# TMS320F28379D_I2C.net
KiCad netlist of a schematic drawn in Altium Designer
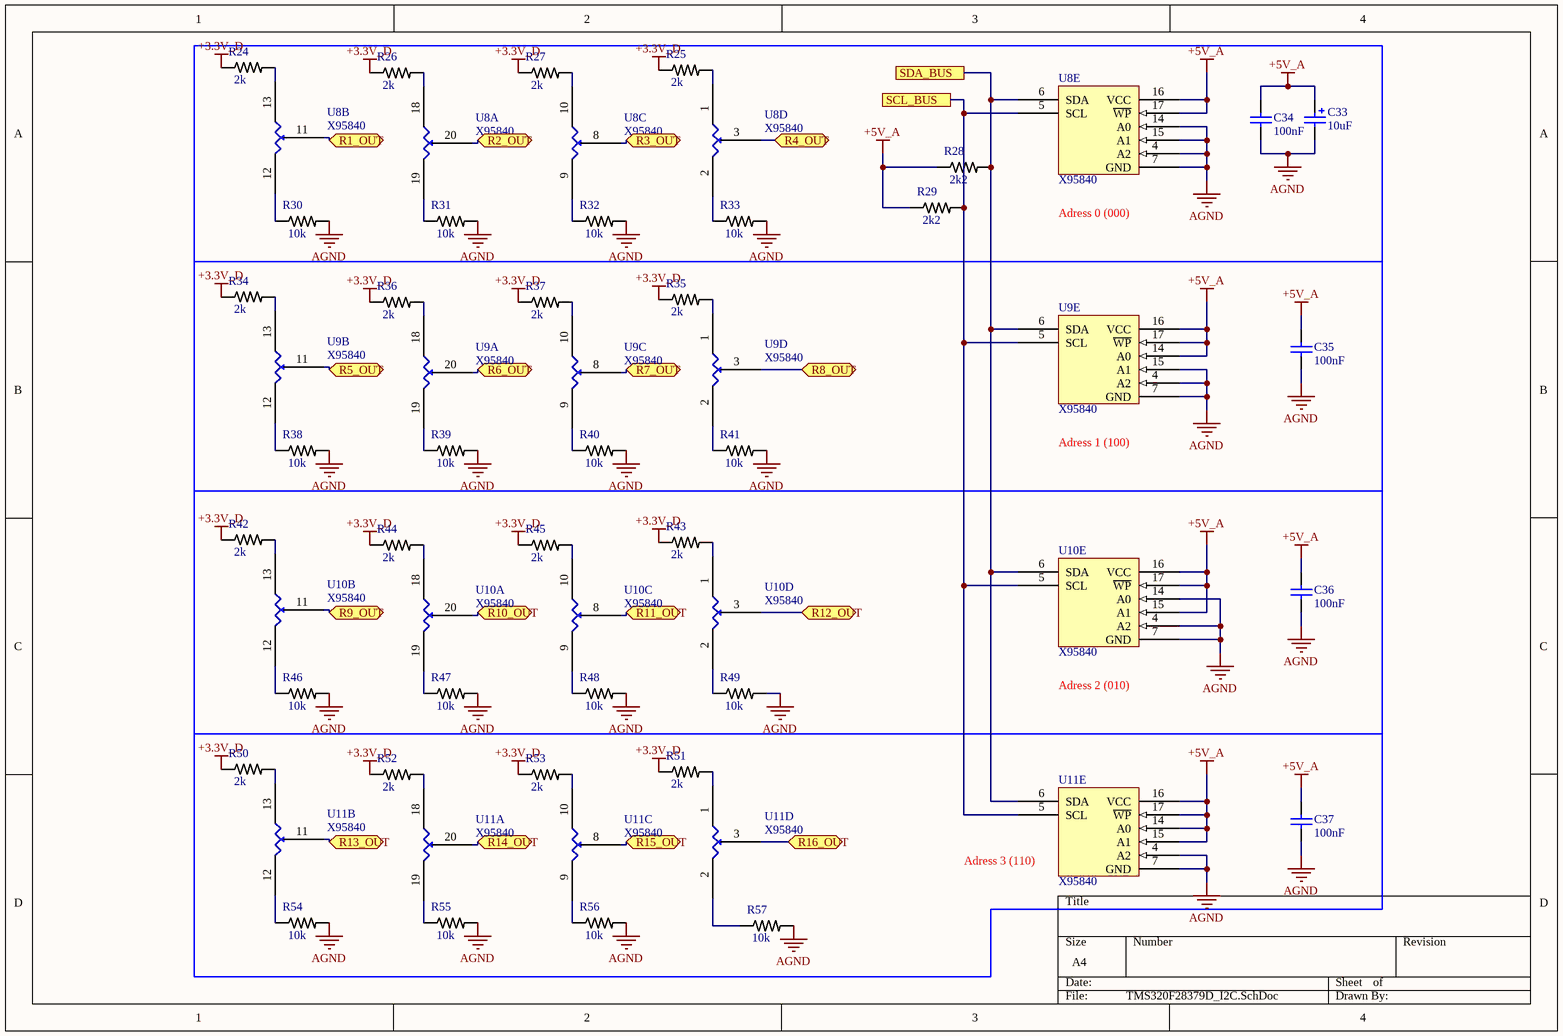
[diagram p0: TMS320F28379D_I2C.SchDoc]

(export (version "E")
  (design (tool "Eeschema 10.0.6"))
  (components
    (comp (ref "C33")
      (value "10uF")
      (footprint "Cap tantalio B")
      (fields (field (name "Comment") "Cap polarizado"))
      (libsource (lib "Condensadores") (part "Cap polarizado"))
    )
    (comp (ref "C34")
      (value "100nF")
      (footprint "CAP 0805")
      (fields (field (name "Comment") "Cap cerámico"))
      (libsource (lib "Condensadores") (part "Cap cerámico"))
    )
    (comp (ref "C35")
      (value "100nF")
      (footprint "CAP 0805")
      (fields (field (name "Comment") "Cap cerámico"))
      (libsource (lib "Condensadores") (part "Cap cerámico"))
    )
    (comp (ref "C36")
      (value "100nF")
      (footprint "CAP 0805")
      (fields (field (name "Comment") "Cap cerámico"))
      (libsource (lib "Condensadores") (part "Cap cerámico"))
    )
    (comp (ref "C37")
      (value "100nF")
      (footprint "CAP 0805")
      (fields (field (name "Comment") "Cap cerámico"))
      (libsource (lib "Condensadores") (part "Cap cerámico"))
    )
    (comp (ref "R24")
      (value "2k")
      (footprint "Resistor 0805")
      (description "Resistor")
      (fields (field (name "Comment") "Resistor 0805"))
      (libsource (lib "Resistencias") (part "Resistor"))
    )
    (comp (ref "R25")
      (value "2k")
      (footprint "Resistor 0805")
      (description "Resistor")
      (fields (field (name "Comment") "Resistor 0805"))
      (libsource (lib "Resistencias") (part "Resistor"))
    )
    (comp (ref "R26")
      (value "2k")
      (footprint "Resistor 0805")
      (description "Resistor")
      (fields (field (name "Comment") "Resistor 0805"))
      (libsource (lib "Resistencias") (part "Resistor"))
    )
    (comp (ref "R27")
      (value "2k")
      (footprint "Resistor 0805")
      (description "Resistor")
      (fields (field (name "Comment") "Resistor 0805"))
      (libsource (lib "Resistencias") (part "Resistor"))
    )
    (comp (ref "R28")
      (value "2k2")
      (footprint "Resistor 0805")
      (description "Resistor")
      (fields (field (name "Comment") "Resistor 0805"))
      (libsource (lib "Resistencias") (part "Resistor"))
    )
    (comp (ref "R29")
      (value "2k2")
      (footprint "Resistor 0805")
      (description "Resistor")
      (fields (field (name "Comment") "Resistor 0805"))
      (libsource (lib "Resistencias") (part "Resistor"))
    )
    (comp (ref "R30")
      (value "10k")
      (footprint "Resistor 0805")
      (description "Resistor")
      (fields (field (name "Comment") "Resistor 0805"))
      (libsource (lib "Resistencias") (part "Resistor"))
    )
    (comp (ref "R31")
      (value "10k")
      (footprint "Resistor 0805")
      (description "Resistor")
      (fields (field (name "Comment") "Resistor 0805"))
      (libsource (lib "Resistencias") (part "Resistor"))
    )
    (comp (ref "R32")
      (value "10k")
      (footprint "Resistor 0805")
      (description "Resistor")
      (fields (field (name "Comment") "Resistor 0805"))
      (libsource (lib "Resistencias") (part "Resistor"))
    )
    (comp (ref "R33")
      (value "10k")
      (footprint "Resistor 0805")
      (description "Resistor")
      (fields (field (name "Comment") "Resistor 0805"))
      (libsource (lib "Resistencias") (part "Resistor"))
    )
    (comp (ref "R34")
      (value "2k")
      (footprint "Resistor 0805")
      (description "Resistor")
      (fields (field (name "Comment") "Resistor 0805"))
      (libsource (lib "Resistencias") (part "Resistor"))
    )
    (comp (ref "R35")
      (value "2k")
      (footprint "Resistor 0805")
      (description "Resistor")
      (fields (field (name "Comment") "Resistor 0805"))
      (libsource (lib "Resistencias") (part "Resistor"))
    )
    (comp (ref "R36")
      (value "2k")
      (footprint "Resistor 0805")
      (description "Resistor")
      (fields (field (name "Comment") "Resistor 0805"))
      (libsource (lib "Resistencias") (part "Resistor"))
    )
    (comp (ref "R37")
      (value "2k")
      (footprint "Resistor 0805")
      (description "Resistor")
      (fields (field (name "Comment") "Resistor 0805"))
      (libsource (lib "Resistencias") (part "Resistor"))
    )
    (comp (ref "R38")
      (value "10k")
      (footprint "Resistor 0805")
      (description "Resistor")
      (fields (field (name "Comment") "Resistor 0805"))
      (libsource (lib "Resistencias") (part "Resistor"))
    )
    (comp (ref "R39")
      (value "10k")
      (footprint "Resistor 0805")
      (description "Resistor")
      (fields (field (name "Comment") "Resistor 0805"))
      (libsource (lib "Resistencias") (part "Resistor"))
    )
    (comp (ref "R40")
      (value "10k")
      (footprint "Resistor 0805")
      (description "Resistor")
      (fields (field (name "Comment") "Resistor 0805"))
      (libsource (lib "Resistencias") (part "Resistor"))
    )
    (comp (ref "R41")
      (value "10k")
      (footprint "Resistor 0805")
      (description "Resistor")
      (fields (field (name "Comment") "Resistor 0805"))
      (libsource (lib "Resistencias") (part "Resistor"))
    )
    (comp (ref "R42")
      (value "2k")
      (footprint "Resistor 0805")
      (description "Resistor")
      (fields (field (name "Comment") "Resistor 0805"))
      (libsource (lib "Resistencias") (part "Resistor"))
    )
    (comp (ref "R43")
      (value "2k")
      (footprint "Resistor 0805")
      (description "Resistor")
      (fields (field (name "Comment") "Resistor 0805"))
      (libsource (lib "Resistencias") (part "Resistor"))
    )
    (comp (ref "R44")
      (value "2k")
      (footprint "Resistor 0805")
      (description "Resistor")
      (fields (field (name "Comment") "Resistor 0805"))
      (libsource (lib "Resistencias") (part "Resistor"))
    )
    (comp (ref "R45")
      (value "2k")
      (footprint "Resistor 0805")
      (description "Resistor")
      (fields (field (name "Comment") "Resistor 0805"))
      (libsource (lib "Resistencias") (part "Resistor"))
    )
    (comp (ref "R46")
      (value "10k")
      (footprint "Resistor 0805")
      (description "Resistor")
      (fields (field (name "Comment") "Resistor 0805"))
      (libsource (lib "Resistencias") (part "Resistor"))
    )
    (comp (ref "R47")
      (value "10k")
      (footprint "Resistor 0805")
      (description "Resistor")
      (fields (field (name "Comment") "Resistor 0805"))
      (libsource (lib "Resistencias") (part "Resistor"))
    )
    (comp (ref "R48")
      (value "10k")
      (footprint "Resistor 0805")
      (description "Resistor")
      (fields (field (name "Comment") "Resistor 0805"))
      (libsource (lib "Resistencias") (part "Resistor"))
    )
    (comp (ref "R49")
      (value "10k")
      (footprint "Resistor 0805")
      (description "Resistor")
      (fields (field (name "Comment") "Resistor 0805"))
      (libsource (lib "Resistencias") (part "Resistor"))
    )
    (comp (ref "R50")
      (value "2k")
      (footprint "Resistor 0805")
      (description "Resistor")
      (fields (field (name "Comment") "Resistor 0805"))
      (libsource (lib "Resistencias") (part "Resistor"))
    )
    (comp (ref "R51")
      (value "2k")
      (footprint "Resistor 0805")
      (description "Resistor")
      (fields (field (name "Comment") "Resistor 0805"))
      (libsource (lib "Resistencias") (part "Resistor"))
    )
    (comp (ref "R52")
      (value "2k")
      (footprint "Resistor 0805")
      (description "Resistor")
      (fields (field (name "Comment") "Resistor 0805"))
      (libsource (lib "Resistencias") (part "Resistor"))
    )
    (comp (ref "R53")
      (value "2k")
      (footprint "Resistor 0805")
      (description "Resistor")
      (fields (field (name "Comment") "Resistor 0805"))
      (libsource (lib "Resistencias") (part "Resistor"))
    )
    (comp (ref "R54")
      (value "10k")
      (footprint "Resistor 0805")
      (description "Resistor")
      (fields (field (name "Comment") "Resistor 0805"))
      (libsource (lib "Resistencias") (part "Resistor"))
    )
    (comp (ref "R55")
      (value "10k")
      (footprint "Resistor 0805")
      (description "Resistor")
      (fields (field (name "Comment") "Resistor 0805"))
      (libsource (lib "Resistencias") (part "Resistor"))
    )
    (comp (ref "R56")
      (value "10k")
      (footprint "Resistor 0805")
      (description "Resistor")
      (fields (field (name "Comment") "Resistor 0805"))
      (libsource (lib "Resistencias") (part "Resistor"))
    )
    (comp (ref "R57")
      (value "10k")
      (footprint "Resistor 0805")
      (description "Resistor")
      (fields (field (name "Comment") "Resistor 0805"))
      (libsource (lib "Resistencias") (part "Resistor"))
    )
    (comp (ref "U8")
      (value "X95840")
      (footprint "20-TSSOP")
      (fields
        (field (name "DIGI-KEY PART NUMBER") "X95840WV20IZ-2.7-ND")
        (field (name "MANUFACTURER PART NUMBER") "X95840WV20IZ-2.7")
      )
      (libsource (lib "Circuitos integrados") (part "X95840"))
    )
    (comp (ref "U9")
      (value "X95840")
      (footprint "20-TSSOP")
      (fields
        (field (name "DIGI-KEY PART NUMBER") "X95840WV20IZ-2.7-ND")
        (field (name "MANUFACTURER PART NUMBER") "X95840WV20IZ-2.7")
      )
      (libsource (lib "Circuitos integrados") (part "X95840"))
    )
    (comp (ref "U10")
      (value "X95840")
      (footprint "20-TSSOP")
      (fields
        (field (name "DIGI-KEY PART NUMBER") "X95840WV20IZ-2.7-ND")
        (field (name "MANUFACTURER PART NUMBER") "X95840WV20IZ-2.7")
      )
      (libsource (lib "Circuitos integrados") (part "X95840"))
    )
    (comp (ref "U11")
      (value "X95840")
      (footprint "20-TSSOP")
      (fields
        (field (name "DIGI-KEY PART NUMBER") "X95840WV20IZ-2.7-ND")
        (field (name "MANUFACTURER PART NUMBER") "X95840WV20IZ-2.7")
      )
      (libsource (lib "Circuitos integrados") (part "X95840"))
    )
  )
  (nets
    (net (code "1") (name "+3.3V_D") (class "Default")
      (node (ref "R24") (pin "1") (pinfunction "1_1") (pintype "passive"))
      (node (ref "R25") (pin "1") (pinfunction "1_1") (pintype "passive"))
      (node (ref "R26") (pin "1") (pinfunction "1_1") (pintype "passive"))
      (node (ref "R27") (pin "1") (pinfunction "1_1") (pintype "passive"))
      (node (ref "R34") (pin "1") (pinfunction "1_1") (pintype "passive"))
      (node (ref "R35") (pin "1") (pinfunction "1_1") (pintype "passive"))
      (node (ref "R36") (pin "1") (pinfunction "1_1") (pintype "passive"))
      (node (ref "R37") (pin "1") (pinfunction "1_1") (pintype "passive"))
      (node (ref "R42") (pin "1") (pinfunction "1_1") (pintype "passive"))
      (node (ref "R43") (pin "1") (pinfunction "1_1") (pintype "passive"))
      (node (ref "R44") (pin "1") (pinfunction "1_1") (pintype "passive"))
      (node (ref "R45") (pin "1") (pinfunction "1_1") (pintype "passive"))
      (node (ref "R50") (pin "1") (pinfunction "1_1") (pintype "passive"))
      (node (ref "R51") (pin "1") (pinfunction "1_1") (pintype "passive"))
      (node (ref "R52") (pin "1") (pinfunction "1_1") (pintype "passive"))
      (node (ref "R53") (pin "1") (pinfunction "1_1") (pintype "passive"))
    )
    (net (code "2") (name "+5V_A") (class "Default")
      (node (ref "C33") (pin "1") (pinfunction "1_1") (pintype "passive"))
      (node (ref "C34") (pin "1") (pinfunction "1_1") (pintype "passive"))
      (node (ref "C35") (pin "1") (pinfunction "1_1") (pintype "passive"))
      (node (ref "C36") (pin "1") (pinfunction "1_1") (pintype "passive"))
      (node (ref "C37") (pin "1") (pinfunction "1_1") (pintype "passive"))
      (node (ref "R28") (pin "1") (pinfunction "1_1") (pintype "passive"))
      (node (ref "R29") (pin "1") (pinfunction "1_1") (pintype "passive"))
      (node (ref "U10") (pin "15") (pinfunction "A1_15") (pintype "input"))
      (node (ref "U10") (pin "16") (pinfunction "VCC_16") (pintype "power_in"))
      (node (ref "U10") (pin "17") (pinfunction "~{WP}_17") (pintype "input"))
      (node (ref "U11") (pin "14") (pinfunction "A0_14") (pintype "input"))
      (node (ref "U11") (pin "15") (pinfunction "A1_15") (pintype "input"))
      (node (ref "U11") (pin "16") (pinfunction "VCC_16") (pintype "power_in"))
      (node (ref "U11") (pin "17") (pinfunction "~{WP}_17") (pintype "input"))
      (node (ref "U8") (pin "16") (pinfunction "VCC_16") (pintype "power_in"))
      (node (ref "U8") (pin "17") (pinfunction "~{WP}_17") (pintype "input"))
      (node (ref "U9") (pin "14") (pinfunction "A0_14") (pintype "input"))
      (node (ref "U9") (pin "16") (pinfunction "VCC_16") (pintype "power_in"))
      (node (ref "U9") (pin "17") (pinfunction "~{WP}_17") (pintype "input"))
    )
    (net (code "3") (name "/R1_OUT") (class "Default")
      (node (ref "U8") (pin "11") (pinfunction "RW1_11") (pintype "passive"))
    )
    (net (code "4") (name "/R2_OUT") (class "Default")
      (node (ref "U8") (pin "20") (pinfunction "20_20") (pintype "passive"))
    )
    (net (code "5") (name "/R3_OUT") (class "Default")
      (node (ref "U8") (pin "8") (pinfunction "RW2_8") (pintype "passive"))
    )
    (net (code "6") (name "/R4_OUT") (class "Default")
      (node (ref "U8") (pin "3") (pinfunction "RW3_3") (pintype "passive"))
    )
    (net (code "7") (name "/R5_OUT") (class "Default")
      (node (ref "U9") (pin "11") (pinfunction "RW1_11") (pintype "passive"))
    )
    (net (code "8") (name "/R6_OUT") (class "Default")
      (node (ref "U9") (pin "20") (pinfunction "20_20") (pintype "passive"))
    )
    (net (code "9") (name "/R7_OUT") (class "Default")
      (node (ref "U9") (pin "8") (pinfunction "RW2_8") (pintype "passive"))
    )
    (net (code "10") (name "/R8_OUT") (class "Default")
      (node (ref "U9") (pin "3") (pinfunction "RW3_3") (pintype "passive"))
    )
    (net (code "11") (name "/R9_OUT") (class "Default")
      (node (ref "U10") (pin "11") (pinfunction "RW1_11") (pintype "passive"))
    )
    (net (code "12") (name "/R10_OUT") (class "Default")
      (node (ref "U10") (pin "20") (pinfunction "20_20") (pintype "passive"))
    )
    (net (code "13") (name "/R11_OUT") (class "Default")
      (node (ref "U10") (pin "8") (pinfunction "RW2_8") (pintype "passive"))
    )
    (net (code "14") (name "/R12_OUT") (class "Default")
      (node (ref "U10") (pin "3") (pinfunction "RW3_3") (pintype "passive"))
    )
    (net (code "15") (name "/R13_OUT") (class "Default")
      (node (ref "U11") (pin "11") (pinfunction "RW1_11") (pintype "passive"))
    )
    (net (code "16") (name "/R14_OUT") (class "Default")
      (node (ref "U11") (pin "20") (pinfunction "20_20") (pintype "passive"))
    )
    (net (code "17") (name "/R15_OUT") (class "Default")
      (node (ref "U11") (pin "8") (pinfunction "RW2_8") (pintype "passive"))
    )
    (net (code "18") (name "/R16_OUT") (class "Default")
      (node (ref "U11") (pin "3") (pinfunction "RW3_3") (pintype "passive"))
    )
    (net (code "19") (name "/SCL_BUS") (class "Default")
      (node (ref "R29") (pin "2") (pinfunction "2_2") (pintype "passive"))
      (node (ref "U10") (pin "5") (pinfunction "SCL_5") (pintype "passive"))
      (node (ref "U11") (pin "5") (pinfunction "SCL_5") (pintype "passive"))
      (node (ref "U8") (pin "5") (pinfunction "SCL_5") (pintype "passive"))
      (node (ref "U9") (pin "5") (pinfunction "SCL_5") (pintype "passive"))
    )
    (net (code "20") (name "/SDA_BUS") (class "Default")
      (node (ref "R28") (pin "2") (pinfunction "2_2") (pintype "passive"))
      (node (ref "U10") (pin "6") (pinfunction "SDA_6") (pintype "passive"))
      (node (ref "U11") (pin "6") (pinfunction "SDA_6") (pintype "passive"))
      (node (ref "U8") (pin "6") (pinfunction "SDA_6") (pintype "passive"))
      (node (ref "U9") (pin "6") (pinfunction "SDA_6") (pintype "passive"))
    )
    (net (code "21") (name "AGND") (class "Default")
      (node (ref "C33") (pin "2") (pinfunction "2_2") (pintype "passive"))
      (node (ref "C34") (pin "2") (pinfunction "2_2") (pintype "passive"))
      (node (ref "C35") (pin "2") (pinfunction "2_2") (pintype "passive"))
      (node (ref "C36") (pin "2") (pinfunction "2_2") (pintype "passive"))
      (node (ref "C37") (pin "2") (pinfunction "2_2") (pintype "passive"))
      (node (ref "R30") (pin "2") (pinfunction "2_2") (pintype "passive"))
      (node (ref "R31") (pin "2") (pinfunction "2_2") (pintype "passive"))
      (node (ref "R32") (pin "2") (pinfunction "2_2") (pintype "passive"))
      (node (ref "R33") (pin "2") (pinfunction "2_2") (pintype "passive"))
      (node (ref "R38") (pin "2") (pinfunction "2_2") (pintype "passive"))
      (node (ref "R39") (pin "2") (pinfunction "2_2") (pintype "passive"))
      (node (ref "R40") (pin "2") (pinfunction "2_2") (pintype "passive"))
      (node (ref "R41") (pin "2") (pinfunction "2_2") (pintype "passive"))
      (node (ref "R46") (pin "2") (pinfunction "2_2") (pintype "passive"))
      (node (ref "R47") (pin "2") (pinfunction "2_2") (pintype "passive"))
      (node (ref "R48") (pin "2") (pinfunction "2_2") (pintype "passive"))
      (node (ref "R49") (pin "2") (pinfunction "2_2") (pintype "passive"))
      (node (ref "R54") (pin "2") (pinfunction "2_2") (pintype "passive"))
      (node (ref "R55") (pin "2") (pinfunction "2_2") (pintype "passive"))
      (node (ref "R56") (pin "2") (pinfunction "2_2") (pintype "passive"))
      (node (ref "R57") (pin "2") (pinfunction "2_2") (pintype "passive"))
      (node (ref "U10") (pin "14") (pinfunction "A0_14") (pintype "input"))
      (node (ref "U10") (pin "4") (pinfunction "A2_4") (pintype "input"))
      (node (ref "U10") (pin "7") (pinfunction "GND_7") (pintype "power_in"))
      (node (ref "U11") (pin "4") (pinfunction "A2_4") (pintype "input"))
      (node (ref "U11") (pin "7") (pinfunction "GND_7") (pintype "power_in"))
      (node (ref "U8") (pin "14") (pinfunction "A0_14") (pintype "input"))
      (node (ref "U8") (pin "15") (pinfunction "A1_15") (pintype "input"))
      (node (ref "U8") (pin "4") (pinfunction "A2_4") (pintype "input"))
      (node (ref "U8") (pin "7") (pinfunction "GND_7") (pintype "power_in"))
      (node (ref "U9") (pin "15") (pinfunction "A1_15") (pintype "input"))
      (node (ref "U9") (pin "4") (pinfunction "A2_4") (pintype "input"))
      (node (ref "U9") (pin "7") (pinfunction "GND_7") (pintype "power_in"))
    )
    (net (code "22") (name "Net-(R26-Pad2)") (class "Default")
      (node (ref "R26") (pin "2") (pinfunction "2_2") (pintype "passive"))
      (node (ref "U8") (pin "18") (pinfunction "18_18") (pintype "passive"))
    )
    (net (code "23") (name "Net-(R31-Pad1)") (class "Default")
      (node (ref "R31") (pin "1") (pinfunction "1_1") (pintype "passive"))
      (node (ref "U8") (pin "19") (pinfunction "19_19") (pintype "passive"))
    )
    (net (code "24") (name "Net-(R36-Pad2)") (class "Default")
      (node (ref "R36") (pin "2") (pinfunction "2_2") (pintype "passive"))
      (node (ref "U9") (pin "18") (pinfunction "18_18") (pintype "passive"))
    )
    (net (code "25") (name "Net-(R39-Pad1)") (class "Default")
      (node (ref "R39") (pin "1") (pinfunction "1_1") (pintype "passive"))
      (node (ref "U9") (pin "19") (pinfunction "19_19") (pintype "passive"))
    )
    (net (code "26") (name "Net-(R44-Pad2)") (class "Default")
      (node (ref "R44") (pin "2") (pinfunction "2_2") (pintype "passive"))
      (node (ref "U10") (pin "18") (pinfunction "18_18") (pintype "passive"))
    )
    (net (code "27") (name "Net-(R47-Pad1)") (class "Default")
      (node (ref "R47") (pin "1") (pinfunction "1_1") (pintype "passive"))
      (node (ref "U10") (pin "19") (pinfunction "19_19") (pintype "passive"))
    )
    (net (code "28") (name "Net-(R52-Pad2)") (class "Default")
      (node (ref "R52") (pin "2") (pinfunction "2_2") (pintype "passive"))
      (node (ref "U11") (pin "18") (pinfunction "18_18") (pintype "passive"))
    )
    (net (code "29") (name "Net-(R55-Pad1)") (class "Default")
      (node (ref "R55") (pin "1") (pinfunction "1_1") (pintype "passive"))
      (node (ref "U11") (pin "19") (pinfunction "19_19") (pintype "passive"))
    )
    (net (code "30") (name "Net-(U8B-RH1)") (class "Default")
      (node (ref "R24") (pin "2") (pinfunction "2_2") (pintype "passive"))
      (node (ref "U8") (pin "13") (pinfunction "RH1_13") (pintype "passive"))
    )
    (net (code "31") (name "Net-(U8B-RL1)") (class "Default")
      (node (ref "R30") (pin "1") (pinfunction "1_1") (pintype "passive"))
      (node (ref "U8") (pin "12") (pinfunction "RL1_12") (pintype "passive"))
    )
    (net (code "32") (name "Net-(U8C-RH2)") (class "Default")
      (node (ref "R27") (pin "2") (pinfunction "2_2") (pintype "passive"))
      (node (ref "U8") (pin "10") (pinfunction "RH2_10") (pintype "passive"))
    )
    (net (code "33") (name "Net-(U8C-RL2)") (class "Default")
      (node (ref "R32") (pin "1") (pinfunction "1_1") (pintype "passive"))
      (node (ref "U8") (pin "9") (pinfunction "RL2_9") (pintype "passive"))
    )
    (net (code "34") (name "Net-(U8D-RH3)") (class "Default")
      (node (ref "R25") (pin "2") (pinfunction "2_2") (pintype "passive"))
      (node (ref "U8") (pin "1") (pinfunction "RH3_1") (pintype "passive"))
    )
    (net (code "35") (name "Net-(U8D-RL3)") (class "Default")
      (node (ref "R33") (pin "1") (pinfunction "1_1") (pintype "passive"))
      (node (ref "U8") (pin "2") (pinfunction "RL3_2") (pintype "passive"))
    )
    (net (code "36") (name "Net-(U9B-RH1)") (class "Default")
      (node (ref "R34") (pin "2") (pinfunction "2_2") (pintype "passive"))
      (node (ref "U9") (pin "13") (pinfunction "RH1_13") (pintype "passive"))
    )
    (net (code "37") (name "Net-(U9B-RL1)") (class "Default")
      (node (ref "R38") (pin "1") (pinfunction "1_1") (pintype "passive"))
      (node (ref "U9") (pin "12") (pinfunction "RL1_12") (pintype "passive"))
    )
    (net (code "38") (name "Net-(U9C-RH2)") (class "Default")
      (node (ref "R37") (pin "2") (pinfunction "2_2") (pintype "passive"))
      (node (ref "U9") (pin "10") (pinfunction "RH2_10") (pintype "passive"))
    )
    (net (code "39") (name "Net-(U9C-RL2)") (class "Default")
      (node (ref "R40") (pin "1") (pinfunction "1_1") (pintype "passive"))
      (node (ref "U9") (pin "9") (pinfunction "RL2_9") (pintype "passive"))
    )
    (net (code "40") (name "Net-(U9D-RH3)") (class "Default")
      (node (ref "R35") (pin "2") (pinfunction "2_2") (pintype "passive"))
      (node (ref "U9") (pin "1") (pinfunction "RH3_1") (pintype "passive"))
    )
    (net (code "41") (name "Net-(U9D-RL3)") (class "Default")
      (node (ref "R41") (pin "1") (pinfunction "1_1") (pintype "passive"))
      (node (ref "U9") (pin "2") (pinfunction "RL3_2") (pintype "passive"))
    )
    (net (code "42") (name "Net-(U10B-RH1)") (class "Default")
      (node (ref "R42") (pin "2") (pinfunction "2_2") (pintype "passive"))
      (node (ref "U10") (pin "13") (pinfunction "RH1_13") (pintype "passive"))
    )
    (net (code "43") (name "Net-(U10B-RL1)") (class "Default")
      (node (ref "R46") (pin "1") (pinfunction "1_1") (pintype "passive"))
      (node (ref "U10") (pin "12") (pinfunction "RL1_12") (pintype "passive"))
    )
    (net (code "44") (name "Net-(U10C-RH2)") (class "Default")
      (node (ref "R45") (pin "2") (pinfunction "2_2") (pintype "passive"))
      (node (ref "U10") (pin "10") (pinfunction "RH2_10") (pintype "passive"))
    )
    (net (code "45") (name "Net-(U10C-RL2)") (class "Default")
      (node (ref "R48") (pin "1") (pinfunction "1_1") (pintype "passive"))
      (node (ref "U10") (pin "9") (pinfunction "RL2_9") (pintype "passive"))
    )
    (net (code "46") (name "Net-(U10D-RH3)") (class "Default")
      (node (ref "R43") (pin "2") (pinfunction "2_2") (pintype "passive"))
      (node (ref "U10") (pin "1") (pinfunction "RH3_1") (pintype "passive"))
    )
    (net (code "47") (name "Net-(U10D-RL3)") (class "Default")
      (node (ref "R49") (pin "1") (pinfunction "1_1") (pintype "passive"))
      (node (ref "U10") (pin "2") (pinfunction "RL3_2") (pintype "passive"))
    )
    (net (code "48") (name "Net-(U11B-RH1)") (class "Default")
      (node (ref "R50") (pin "2") (pinfunction "2_2") (pintype "passive"))
      (node (ref "U11") (pin "13") (pinfunction "RH1_13") (pintype "passive"))
    )
    (net (code "49") (name "Net-(U11B-RL1)") (class "Default")
      (node (ref "R54") (pin "1") (pinfunction "1_1") (pintype "passive"))
      (node (ref "U11") (pin "12") (pinfunction "RL1_12") (pintype "passive"))
    )
    (net (code "50") (name "Net-(U11C-RH2)") (class "Default")
      (node (ref "R53") (pin "2") (pinfunction "2_2") (pintype "passive"))
      (node (ref "U11") (pin "10") (pinfunction "RH2_10") (pintype "passive"))
    )
    (net (code "51") (name "Net-(U11C-RL2)") (class "Default")
      (node (ref "R56") (pin "1") (pinfunction "1_1") (pintype "passive"))
      (node (ref "U11") (pin "9") (pinfunction "RL2_9") (pintype "passive"))
    )
    (net (code "52") (name "Net-(U11D-RH3)") (class "Default")
      (node (ref "R51") (pin "2") (pinfunction "2_2") (pintype "passive"))
      (node (ref "U11") (pin "1") (pinfunction "RH3_1") (pintype "passive"))
    )
    (net (code "53") (name "Net-(U11D-RL3)") (class "Default")
      (node (ref "R57") (pin "1") (pinfunction "1_1") (pintype "passive"))
      (node (ref "U11") (pin "2") (pinfunction "RL3_2") (pintype "passive"))
    )
  )
)
